# GPS.net
KiCad netlist of a schematic drawn in Altium Designer
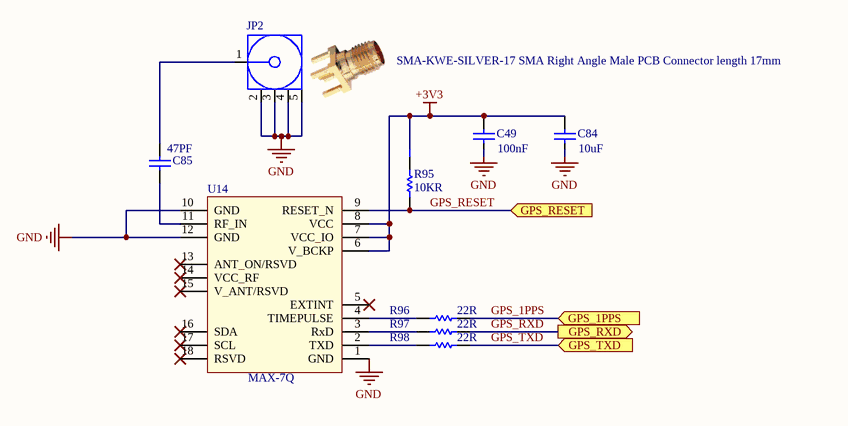
[diagram p0: GPS.SchDoc]

(export (version "E")
  (design (tool "Eeschema 10.0.6"))
  (components
    (comp (ref "C49")
      (value "100nF")
      (footprint "C0603E")
      (description "Chip Monolithic Ceramic Capacitor; SMD")
      (fields
        (field (name "MANUFACTURER") "Murata Electronics North America")
        (field (name "PART NUMBER") "100nF")
        (field (name "MANUFACTURER PART NUMBER") "GRM188R71C104KA01D")
      )
      (libsource (lib "Miscellaneous Devices") (part "Cap"))
    )
    (comp (ref "C84")
      (value "10uF")
      (footprint "C0805E")
      (description "Chip Monolithic Ceramic Capacitor; SMD")
      (fields
        (field (name "MANUFACTURER") "Murata Electronics North America")
        (field (name "PART NUMBER") "10uF")
        (field (name "MANUFACTURER PART NUMBER") "GRM188R71C104KA01D")
      )
      (libsource (lib "Miscellaneous Devices") (part "Cap"))
    )
    (comp (ref "C85")
      (value "47PF")
      (footprint "C0603E")
      (description "Chip Monolithic Ceramic Capacitor; SMD")
      (fields
        (field (name "MANUFACTURER") "Murata Electronics North America")
        (field (name "PART NUMBER") "47PF")
        (field (name "MANUFACTURER PART NUMBER") "GRM188R71C104KA01D")
      )
      (libsource (lib "Miscellaneous Devices") (part "Cap"))
    )
    (comp (ref "JP2")
      (value "SMA-KWE-SILVER-17 SMA Right Angle Male PCB Connector length 17mm")
      (footprint "SMA_R")
      (description "CONN RP-SMA JACK R/A 50 OHM PCB MALE PIN-SILVER")
      (fields
        (field (name "PART NUMBER") "SMA-KWE-SILVER-17 SMA Right Angle Male PCB Connector length 17mm")
        (field (name "MANUFACTURER") "China")
        (field (name "MANUFACTURER PART NUMBER") "SMA-KWE-17 SMA Right Angle Male PCB Connector length 17mm")
      )
      (libsource (lib "Main_Lib") (part "19-46-2-TGG"))
    )
    (comp (ref "R95")
      (value "10KR")
      (footprint "R0603E")
      (description "Resistor: thick film; SMD")
      (fields (field (name "MANUFACTURER") "Yageo") (field (name "PART NUMBER") "10KR"))
      (libsource (lib "Miscellaneous Devices") (part "Res1"))
    )
    (comp (ref "R96")
      (value "22R")
      (footprint "R0603E")
      (description "Resistor: thick film; SMD")
      (fields (field (name "MANUFACTURER") "Yageo") (field (name "PART NUMBER") "22R"))
      (libsource (lib "Miscellaneous Devices") (part "Res1"))
    )
    (comp (ref "R97")
      (value "22R")
      (footprint "R0603E")
      (description "Resistor: thick film; SMD")
      (fields (field (name "MANUFACTURER") "Yageo") (field (name "PART NUMBER") "22R"))
      (libsource (lib "Miscellaneous Devices") (part "Res1"))
    )
    (comp (ref "R98")
      (value "22R")
      (footprint "R0603E")
      (description "Resistor: thick film; SMD")
      (fields (field (name "MANUFACTURER") "Yageo") (field (name "PART NUMBER") "22R"))
      (libsource (lib "Miscellaneous Devices") (part "Res1"))
    )
    (comp (ref "U14")
      (value "GPS_MAX-7Q")
      (footprint "MAX")
      (description "GPS chip module EPP0910")
      (fields (field (name "PART NUMBER") "MAX-7Q") (field (name "MANUFACTURER") "NULL"))
      (libsource (lib "Main_Lib") (part "MAX"))
    )
  )
  (nets
    (net (code "1") (name "+3V3") (class "Default")
      (node (ref "C49") (pin "1") (pinfunction "1_1") (pintype "passive"))
      (node (ref "C84") (pin "1") (pinfunction "1_1") (pintype "passive"))
      (node (ref "R95") (pin "2") (pinfunction "2_2") (pintype "passive"))
      (node (ref "U14") (pin "6") (pinfunction "V_BCKP_6") (pintype "passive"))
      (node (ref "U14") (pin "7") (pinfunction "VCC_IO_7") (pintype "passive"))
      (node (ref "U14") (pin "8") (pinfunction "VCC_8") (pintype "passive"))
    )
    (net (code "2") (name "/GPS_1PPS") (class "Default")
      (node (ref "R96") (pin "2") (pinfunction "2_2") (pintype "passive"))
    )
    (net (code "3") (name "/GPS_RESET") (class "Default")
      (node (ref "R95") (pin "1") (pinfunction "1_1") (pintype "passive"))
      (node (ref "U14") (pin "9") (pinfunction "RESET_N_9") (pintype "passive"))
    )
    (net (code "4") (name "/GPS_RXD") (class "Default")
      (node (ref "R97") (pin "2") (pinfunction "2_2") (pintype "passive"))
    )
    (net (code "5") (name "/GPS_TXD") (class "Default")
      (node (ref "R98") (pin "2") (pinfunction "2_2") (pintype "passive"))
    )
    (net (code "6") (name "GND") (class "Default")
      (node (ref "C49") (pin "2") (pinfunction "2_2") (pintype "passive"))
      (node (ref "C84") (pin "2") (pinfunction "2_2") (pintype "passive"))
      (node (ref "JP2") (pin "2") (pinfunction "GND_2") (pintype "power_in"))
      (node (ref "JP2") (pin "3") (pinfunction "GND_3") (pintype "power_in"))
      (node (ref "JP2") (pin "4") (pinfunction "GND_4") (pintype "power_in"))
      (node (ref "JP2") (pin "5") (pinfunction "GND_5") (pintype "power_in"))
      (node (ref "U14") (pin "1") (pinfunction "GND_1") (pintype "passive"))
      (node (ref "U14") (pin "10") (pinfunction "GND_10") (pintype "passive"))
      (node (ref "U14") (pin "12") (pinfunction "GND_12") (pintype "passive"))
    )
    (net (code "7") (name "Net-(JP2-Signal)") (class "Default")
      (node (ref "C85") (pin "1") (pinfunction "1_1") (pintype "passive"))
      (node (ref "JP2") (pin "1") (pinfunction "Signal_1") (pintype "passive"))
    )
    (net (code "8") (name "Net-(U14-RF_IN)") (class "Default")
      (node (ref "C85") (pin "2") (pinfunction "2_2") (pintype "passive"))
      (node (ref "U14") (pin "11") (pinfunction "RF_IN_11") (pintype "passive"))
    )
    (net (code "9") (name "Net-(U14-RxD)") (class "Default")
      (node (ref "R97") (pin "1") (pinfunction "1_1") (pintype "passive"))
      (node (ref "U14") (pin "3") (pinfunction "RxD_3") (pintype "passive"))
    )
    (net (code "10") (name "Net-(U14-TIMEPULSE)") (class "Default")
      (node (ref "R96") (pin "1") (pinfunction "1_1") (pintype "passive"))
      (node (ref "U14") (pin "4") (pinfunction "TIMEPULSE_4") (pintype "passive"))
    )
    (net (code "11") (name "Net-(U14-TXD)") (class "Default")
      (node (ref "R98") (pin "1") (pinfunction "1_1") (pintype "passive"))
      (node (ref "U14") (pin "2") (pinfunction "TXD_2") (pintype "passive"))
    )
    (net (code "12") (name "unconnected-(U14-ANT_ON{slash}RSVD-Pad13)") (class "Default")
      (node (ref "U14") (pin "13") (pinfunction "ANT_ON/RSVD_13") (pintype "passive+no_connect"))
    )
    (net (code "13") (name "unconnected-(U14-EXTINT-Pad5)") (class "Default")
      (node (ref "U14") (pin "5") (pinfunction "EXTINT_5") (pintype "passive+no_connect"))
    )
    (net (code "14") (name "unconnected-(U14-RSVD-Pad18)") (class "Default")
      (node (ref "U14") (pin "18") (pinfunction "RSVD_18") (pintype "passive+no_connect"))
    )
    (net (code "15") (name "unconnected-(U14-SCL-Pad17)") (class "Default")
      (node (ref "U14") (pin "17") (pinfunction "SCL_17") (pintype "passive+no_connect"))
    )
    (net (code "16") (name "unconnected-(U14-SDA-Pad16)") (class "Default")
      (node (ref "U14") (pin "16") (pinfunction "SDA_16") (pintype "passive+no_connect"))
    )
    (net (code "17") (name "unconnected-(U14-VCC_RF-Pad14)") (class "Default")
      (node (ref "U14") (pin "14") (pinfunction "VCC_RF_14") (pintype "passive+no_connect"))
    )
    (net (code "18") (name "unconnected-(U14-V_ANT{slash}RSVD-Pad15)") (class "Default")
      (node (ref "U14") (pin "15") (pinfunction "V_ANT/RSVD_15") (pintype "passive+no_connect"))
    )
  )
)
